# Dino.net
KiCad netlist of a schematic drawn in EasyEDA
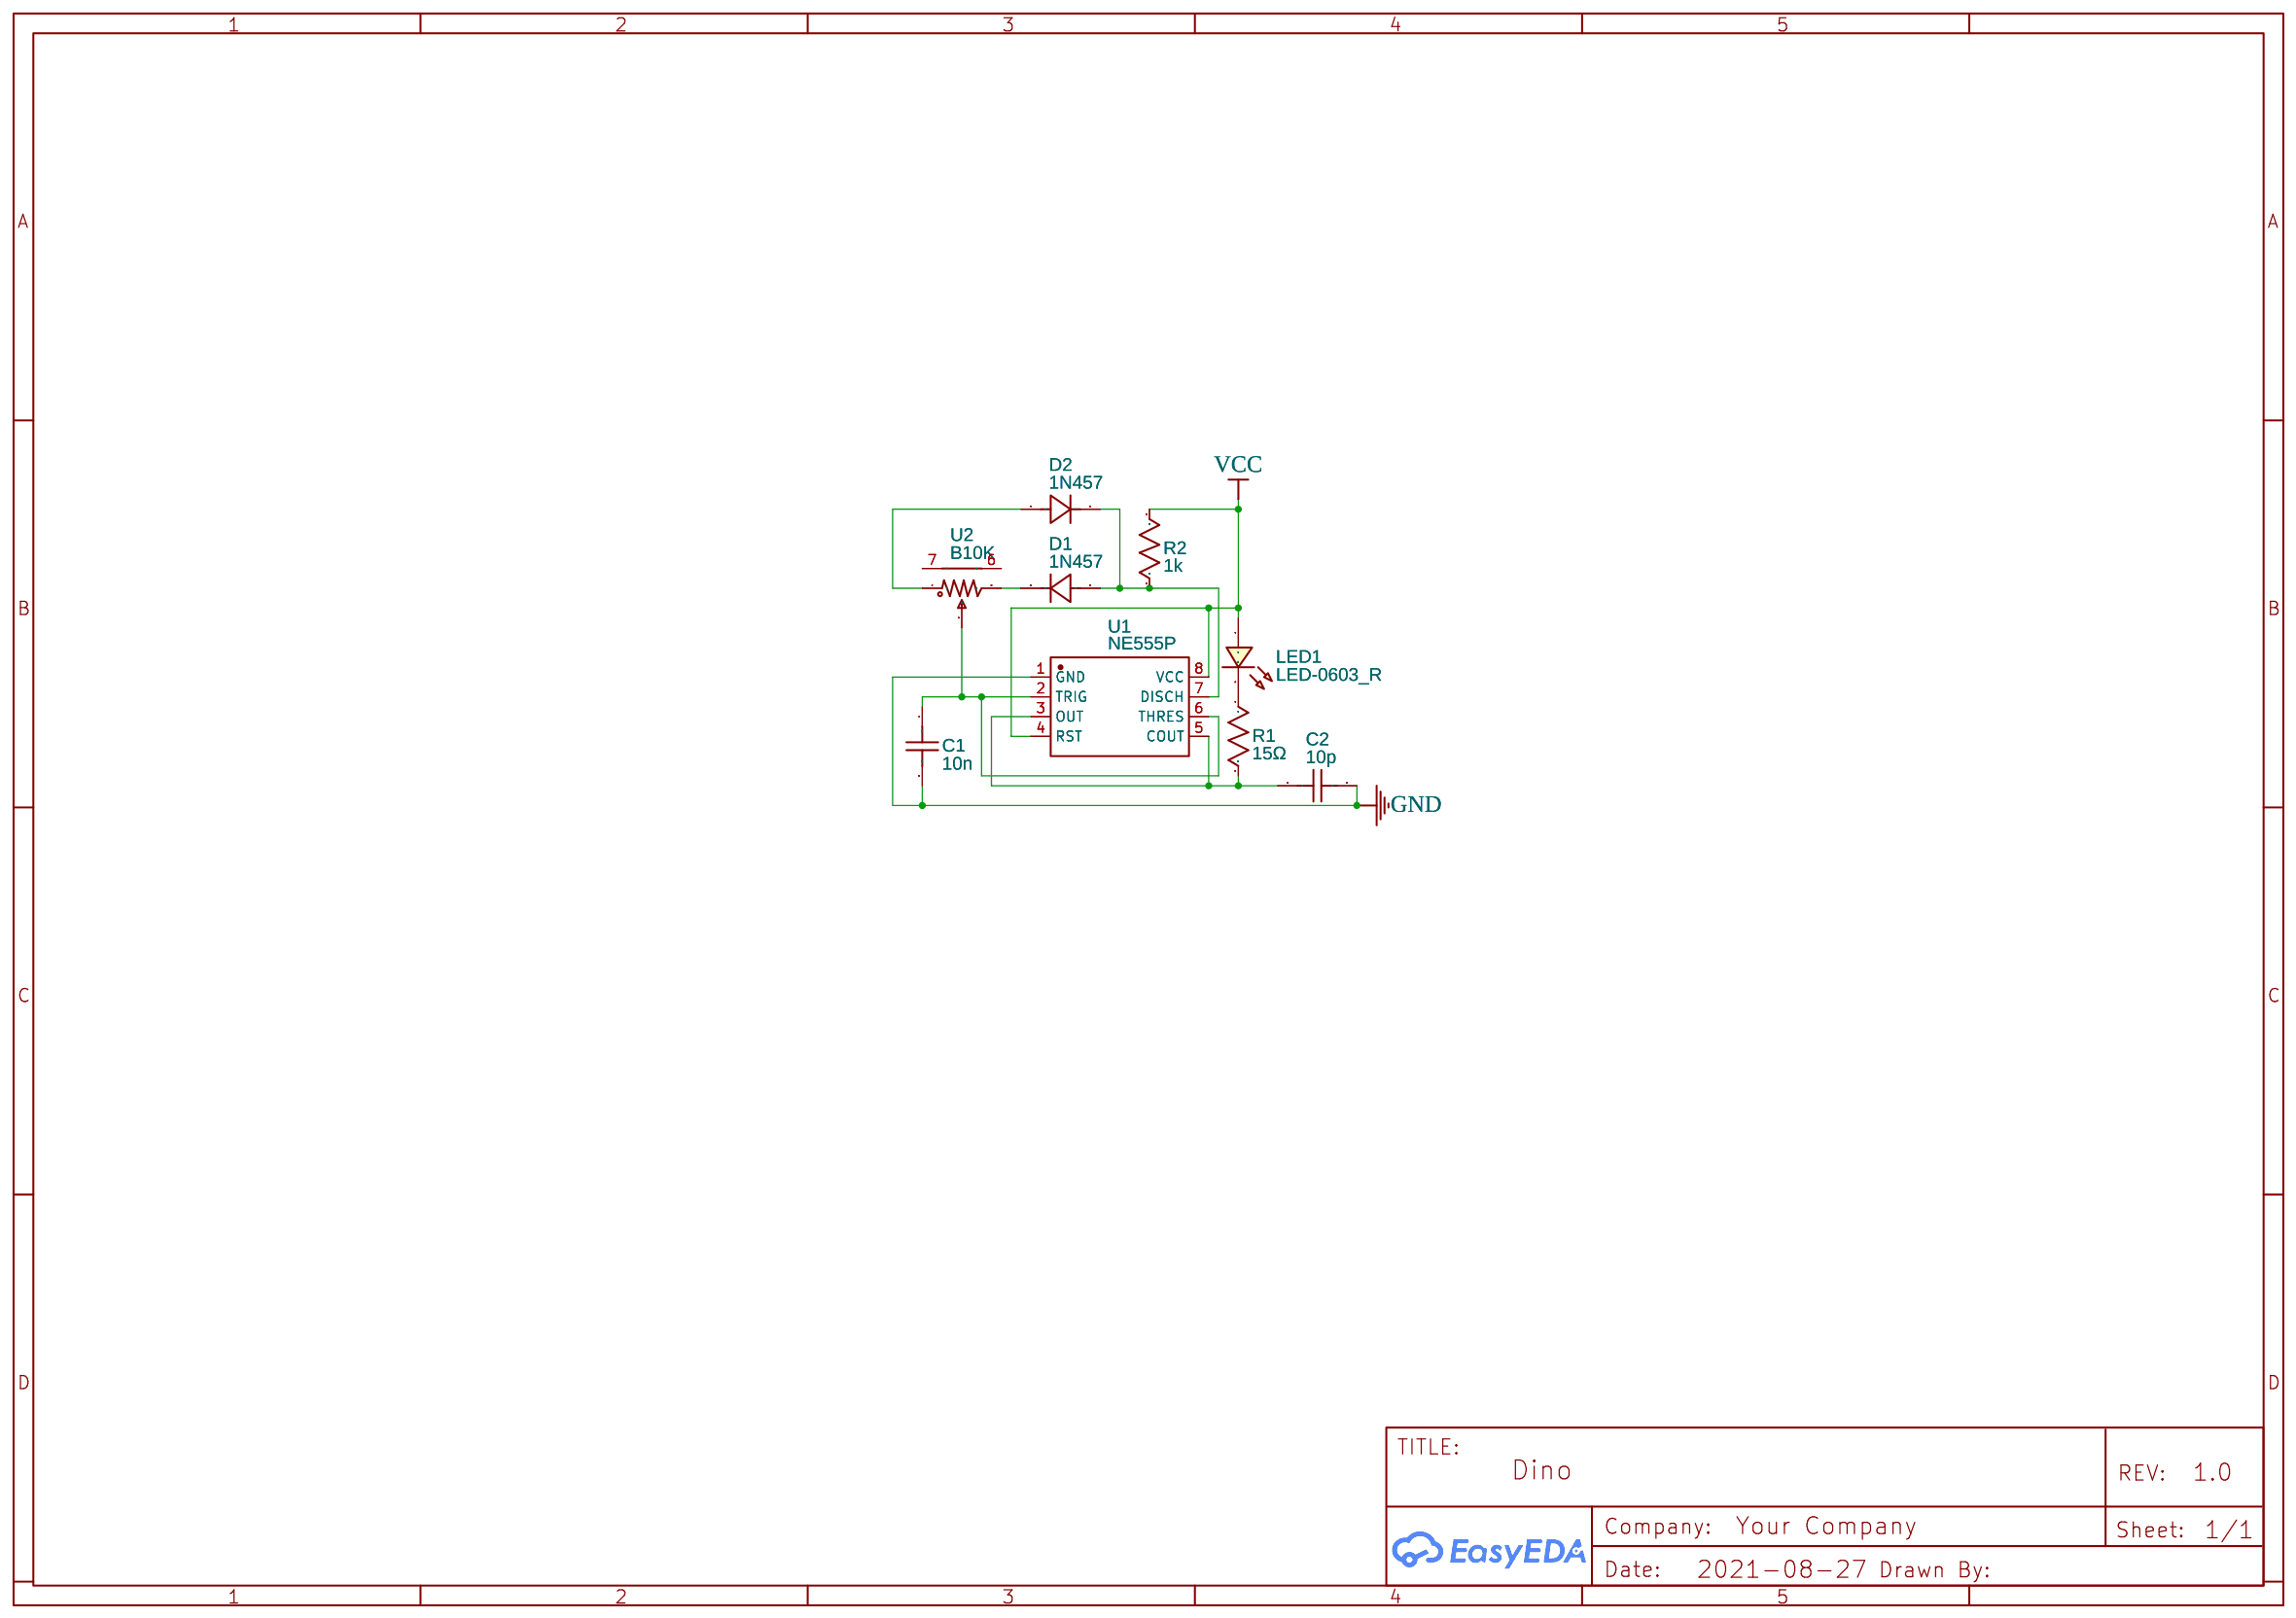
[diagram p0: schematic sheet]

(export (version "E")
  (design (tool "Eeschema 10.0.6"))
  (components
    (comp (ref "C1") (value "10n") (libsource (lib "") (part "C_0603_US")))
    (comp (ref "C2") (value "10p") (libsource (lib "") (part "C_0603_US_1")))
    (comp (ref "D1")
      (value "1N457")
      (fields (field (name "BOM_Supplier Part") "C895219"))
      (libsource (lib "") (part "1N457"))
    )
    (comp (ref "D2")
      (value "1N457")
      (fields (field (name "BOM_Supplier Part") "C895219"))
      (libsource (lib "") (part "1N457_1"))
    )
    (comp (ref "LED1")
      (value "LED-0603_R")
      (fields
        (field (name "BOM_Manufacturer Part") "19-217/R6C-AL1M2VY/3T")
        (field (name "BOM_Supplier Part") "C72044")
      )
      (libsource (lib "") (part "LED-0603_R"))
    )
    (comp (ref "R1") (value "15Ω") (libsource (lib "") (part "R_0603_US_1")))
    (comp (ref "R2") (value "1k") (libsource (lib "") (part "R_0603_US")))
    (comp (ref "U1")
      (value "NE555P")
      (fields (field (name "BOM_Supplier Part") "C46749"))
      (libsource (lib "") (part "NE555P"))
    )
    (comp (ref "U2")
      (value "B10K")
      (fields (field (name "BOM_Supplier Part") "C2839839"))
      (libsource (lib "") (part "B10K"))
    )
  )
  (nets
    (net (code "1") (name "GND") (class "Default")
      (node (ref "C1") (pin "2") (pinfunction "2_2") (pintype "unspecified"))
      (node (ref "C2") (pin "2") (pinfunction "2_2") (pintype "unspecified"))
      (node (ref "U1") (pin "1") (pinfunction "GND_1") (pintype "unspecified"))
    )
    (net (code "2") (name "Net-(D1-A)") (class "Default")
      (node (ref "D1") (pin "2") (pinfunction "A_2") (pintype "unspecified"))
      (node (ref "U2") (pin "3") (pinfunction "3_3") (pintype "unspecified"))
    )
    (net (code "3") (name "Net-(D1-K)") (class "Default")
      (node (ref "D1") (pin "1") (pinfunction "K_1") (pintype "unspecified"))
      (node (ref "D2") (pin "2") (pinfunction "A_2") (pintype "unspecified"))
      (node (ref "R2") (pin "1") (pinfunction "1_1") (pintype "unspecified"))
      (node (ref "U1") (pin "7") (pinfunction "DISCH_7") (pintype "unspecified"))
    )
    (net (code "4") (name "Net-(D2-K)") (class "Default")
      (node (ref "D2") (pin "1") (pinfunction "K_1") (pintype "unspecified"))
      (node (ref "U2") (pin "1") (pinfunction "1_1") (pintype "unspecified"))
    )
    (net (code "5") (name "Net-(LED1-Pad2)") (class "Default")
      (node (ref "LED1") (pin "2") (pinfunction "2_2") (pintype "unspecified"))
      (node (ref "R1") (pin "1") (pinfunction "1_1") (pintype "unspecified"))
    )
    (net (code "6") (name "Net-(U1-COUT)") (class "Default")
      (node (ref "C2") (pin "1") (pinfunction "1_1") (pintype "unspecified"))
      (node (ref "R1") (pin "2") (pinfunction "2_2") (pintype "unspecified"))
      (node (ref "U1") (pin "3") (pinfunction "OUT_3") (pintype "unspecified"))
      (node (ref "U1") (pin "5") (pinfunction "COUT_5") (pintype "unspecified"))
    )
    (net (code "7") (name "Net-(U1-THRES)") (class "Default")
      (node (ref "C1") (pin "1") (pinfunction "1_1") (pintype "unspecified"))
      (node (ref "U1") (pin "2") (pinfunction "TRIG_2") (pintype "unspecified"))
      (node (ref "U1") (pin "6") (pinfunction "THRES_6") (pintype "unspecified"))
      (node (ref "U2") (pin "2") (pinfunction "2_2") (pintype "unspecified"))
    )
    (net (code "8") (name "VCC") (class "Default")
      (node (ref "LED1") (pin "1") (pinfunction "1_1") (pintype "unspecified"))
      (node (ref "R2") (pin "2") (pinfunction "2_2") (pintype "unspecified"))
      (node (ref "U1") (pin "4") (pinfunction "RST_4") (pintype "unspecified"))
      (node (ref "U1") (pin "8") (pinfunction "VCC_8") (pintype "unspecified"))
    )
    (net (code "9") (name "unconnected-(U2-Pad6)") (class "Default")
      (node (ref "U2") (pin "6") (pinfunction "6_6") (pintype "unspecified"))
    )
    (net (code "10") (name "unconnected-(U2-Pad7)") (class "Default")
      (node (ref "U2") (pin "7") (pinfunction "7_7") (pintype "unspecified"))
    )
  )
)
